# Pedalshield_Project_Schematic.net
KiCad netlist of a schematic drawn in Altium Designer
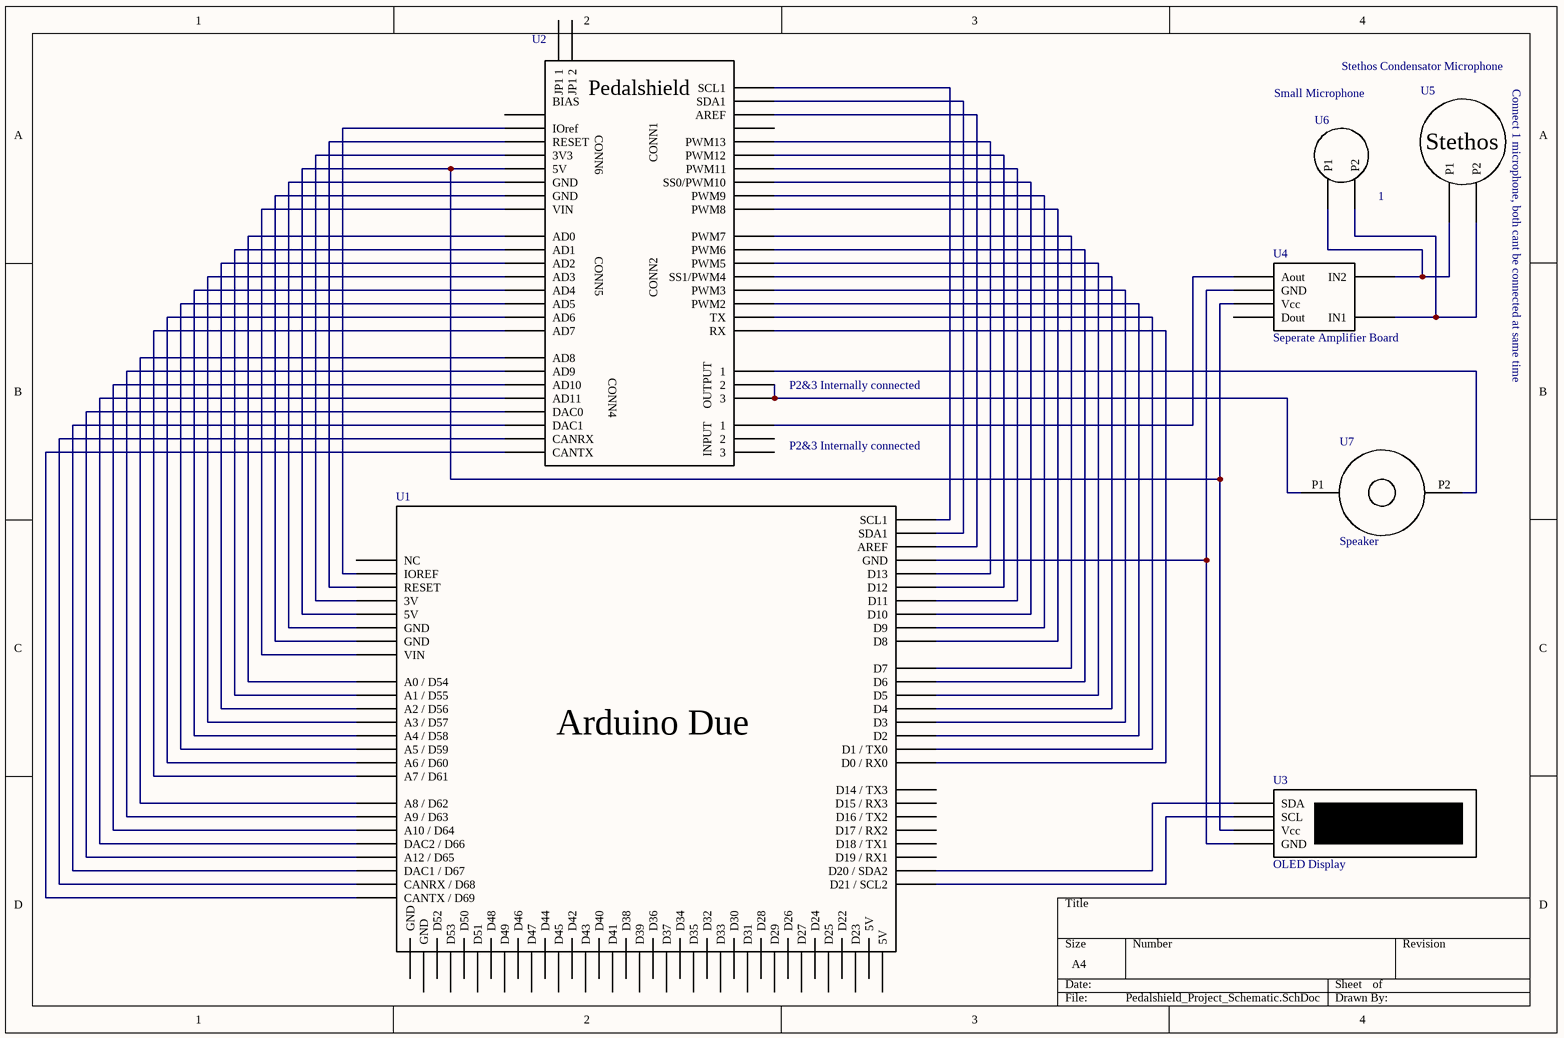
[diagram p0: Pedalshield_Project_Schematic.SchDoc]

(export (version "E")
  (design (tool "Eeschema 10.0.6"))
  (components
    (comp (ref "U1") (value "Arduino Due") (libsource (lib "Schlib1") (part "Arduino Due")))
    (comp (ref "U2") (value "1") (libsource (lib "Schlib1") (part "Pedalshield")))
    (comp (ref "U3") (value "OLED Display") (libsource (lib "Schlib1") (part "OLED Display")))
    (comp (ref "U4")
      (value "Seperate Amplifier Board")
      (libsource (lib "Schlib1") (part "Seperate Amplifier Board"))
    )
    (comp (ref "U5")
      (value "Stethos Condensator Microphone")
      (libsource (lib "Schlib1") (part "Stethos Condensator Microphone"))
    )
    (comp (ref "U6") (value "Small Microphone") (libsource (lib "Schlib1") (part "Small Microphone")))
    (comp (ref "U7") (value "Speaker") (libsource (lib "Schlib1") (part "Speaker")))
  )
  (nets
    (net (code "1") (name "Net-(U1-3V)") (class "Default")
      (node (ref "U1") (pin "SDA5") (pinfunction "3V_SDA5") (pintype "passive"))
      (node (ref "U2") (pin "SDA103") (pinfunction "3V3_SDA103") (pintype "passive"))
    )
    (net (code "2") (name "Net-(U1-A0_{slash}_D54)") (class "Default")
      (node (ref "U1") (pin "SDA11") (pinfunction "A0_/_D54_SDA11") (pintype "passive"))
      (node (ref "U2") (pin "SDA108") (pinfunction "AD0_SDA108") (pintype "passive"))
    )
    (net (code "3") (name "Net-(U1-A1_{slash}_D55)") (class "Default")
      (node (ref "U1") (pin "SDA12") (pinfunction "A1_/_D55_SDA12") (pintype "passive"))
      (node (ref "U2") (pin "SDA109") (pinfunction "AD1_SDA109") (pintype "passive"))
    )
    (net (code "4") (name "Net-(U1-A2_{slash}_D56)") (class "Default")
      (node (ref "U1") (pin "SDA13") (pinfunction "A2_/_D56_SDA13") (pintype "passive"))
      (node (ref "U2") (pin "SDA110") (pinfunction "AD2_SDA110") (pintype "passive"))
    )
    (net (code "5") (name "Net-(U1-A3_{slash}_D57)") (class "Default")
      (node (ref "U1") (pin "SDA14") (pinfunction "A3_/_D57_SDA14") (pintype "passive"))
      (node (ref "U2") (pin "SDA111") (pinfunction "AD3_SDA111") (pintype "passive"))
    )
    (net (code "6") (name "Net-(U1-A4_{slash}_D58)") (class "Default")
      (node (ref "U1") (pin "SDA15") (pinfunction "A4_/_D58_SDA15") (pintype "passive"))
      (node (ref "U2") (pin "SDA112") (pinfunction "AD4_SDA112") (pintype "passive"))
    )
    (net (code "7") (name "Net-(U1-A5_{slash}_D59)") (class "Default")
      (node (ref "U1") (pin "SDA16") (pinfunction "A5_/_D59_SDA16") (pintype "passive"))
      (node (ref "U2") (pin "SDA113") (pinfunction "AD5_SDA113") (pintype "passive"))
    )
    (net (code "8") (name "Net-(U1-A6_{slash}_D60)") (class "Default")
      (node (ref "U1") (pin "SDA17") (pinfunction "A6_/_D60_SDA17") (pintype "passive"))
      (node (ref "U2") (pin "SDA114") (pinfunction "AD6_SDA114") (pintype "passive"))
    )
    (net (code "9") (name "Net-(U1-A7_{slash}_D61)") (class "Default")
      (node (ref "U1") (pin "SDA18") (pinfunction "A7_/_D61_SDA18") (pintype "passive"))
      (node (ref "U2") (pin "SDA115") (pinfunction "AD7_SDA115") (pintype "passive"))
    )
    (net (code "10") (name "Net-(U1-A8_{slash}_D62)") (class "Default")
      (node (ref "U1") (pin "SDA20") (pinfunction "A8_/_D62_SDA20") (pintype "passive"))
      (node (ref "U2") (pin "SDA97") (pinfunction "AD8_SDA97") (pintype "passive"))
    )
    (net (code "11") (name "Net-(U1-A9_{slash}_D63)") (class "Default")
      (node (ref "U1") (pin "SDA21") (pinfunction "A9_/_D63_SDA21") (pintype "passive"))
      (node (ref "U2") (pin "SDA96") (pinfunction "AD9_SDA96") (pintype "passive"))
    )
    (net (code "12") (name "Net-(U1-A10_{slash}_D64)") (class "Default")
      (node (ref "U1") (pin "SDA22") (pinfunction "A10_/_D64_SDA22") (pintype "passive"))
      (node (ref "U2") (pin "SDA95") (pinfunction "AD10_SDA95") (pintype "passive"))
    )
    (net (code "13") (name "Net-(U1-A12_{slash}_D65)") (class "Default")
      (node (ref "U1") (pin "SDA24") (pinfunction "A12_/_D65_SDA24") (pintype "passive"))
      (node (ref "U2") (pin "SDA93") (pinfunction "DAC0_SDA93") (pintype "passive"))
    )
    (net (code "14") (name "Net-(U1-CANRX_{slash}_D68)") (class "Default")
      (node (ref "U1") (pin "SDA26") (pinfunction "CANRX_/_D68_SDA26") (pintype "passive"))
      (node (ref "U2") (pin "SDA91") (pinfunction "CANRX_SDA91") (pintype "passive"))
    )
    (net (code "15") (name "Net-(U1-CANTX_{slash}_D69)") (class "Default")
      (node (ref "U1") (pin "SDA27") (pinfunction "CANTX_/_D69_SDA27") (pintype "passive"))
      (node (ref "U2") (pin "SDA90") (pinfunction "CANTX_SDA90") (pintype "passive"))
    )
    (net (code "16") (name "Net-(U1-D0_{slash}_RX0)") (class "Default")
      (node (ref "U1") (pin "29") (pinfunction "D0_/_RX0_29") (pintype "passive"))
      (node (ref "U2") (pin "SDA88") (pinfunction "RX_SDA88") (pintype "passive"))
    )
    (net (code "17") (name "Net-(U1-D1_{slash}_TX0)") (class "Default")
      (node (ref "U1") (pin "28") (pinfunction "D1_/_TX0_28") (pintype "passive"))
      (node (ref "U2") (pin "SDA87") (pinfunction "TX_SDA87") (pintype "passive"))
    )
    (net (code "18") (name "Net-(U1-D2)") (class "Default")
      (node (ref "U1") (pin "27") (pinfunction "D2_27") (pintype "passive"))
      (node (ref "U2") (pin "SDA118") (pinfunction "PWM2_SDA118") (pintype "passive"))
    )
    (net (code "19") (name "Net-(U1-D3)") (class "Default")
      (node (ref "U1") (pin "26") (pinfunction "D3_26") (pintype "passive"))
      (node (ref "U2") (pin "SDA86") (pinfunction "PWM3_SDA86") (pintype "passive"))
    )
    (net (code "20") (name "Net-(U1-D4)") (class "Default")
      (node (ref "U1") (pin "25") (pinfunction "D4_25") (pintype "passive"))
      (node (ref "U2") (pin "SDA85") (pinfunction "SS1/PWM4_SDA85") (pintype "passive"))
    )
    (net (code "21") (name "Net-(U1-D5)") (class "Default")
      (node (ref "U1") (pin "24") (pinfunction "D5_24") (pintype "passive"))
      (node (ref "U2") (pin "SDA84") (pinfunction "PWM5_SDA84") (pintype "passive"))
    )
    (net (code "22") (name "Net-(U1-D6)") (class "Default")
      (node (ref "U1") (pin "23") (pinfunction "D6_23") (pintype "passive"))
      (node (ref "U2") (pin "SDA83") (pinfunction "PWM6_SDA83") (pintype "passive"))
    )
    (net (code "23") (name "Net-(U1-D7)") (class "Default")
      (node (ref "U1") (pin "22") (pinfunction "D7_22") (pintype "passive"))
      (node (ref "U2") (pin "SDA82") (pinfunction "PWM7_SDA82") (pintype "passive"))
    )
    (net (code "24") (name "Net-(U1-D8)") (class "Default")
      (node (ref "U1") (pin "21") (pinfunction "D8_21") (pintype "passive"))
      (node (ref "U2") (pin "SDA117") (pinfunction "PWM8_SDA117") (pintype "passive"))
    )
    (net (code "25") (name "Net-(U1-D9)") (class "Default")
      (node (ref "U1") (pin "20") (pinfunction "D9_20") (pintype "passive"))
      (node (ref "U2") (pin "SDA116") (pinfunction "PWM9_SDA116") (pintype "passive"))
    )
    (net (code "26") (name "Net-(U1-D10)") (class "Default")
      (node (ref "U1") (pin "19") (pinfunction "D10_19") (pintype "passive"))
      (node (ref "U2") (pin "SDA81") (pinfunction "SS0/PWM10_SDA81") (pintype "passive"))
    )
    (net (code "27") (name "Net-(U1-D11)") (class "Default")
      (node (ref "U1") (pin "18") (pinfunction "D11_18") (pintype "passive"))
      (node (ref "U2") (pin "SDA80") (pinfunction "PWM11_SDA80") (pintype "passive"))
    )
    (net (code "28") (name "Net-(U1-D12)") (class "Default")
      (node (ref "U1") (pin "17") (pinfunction "D12_17") (pintype "passive"))
      (node (ref "U2") (pin "SDA79") (pinfunction "PWM12_SDA79") (pintype "passive"))
    )
    (net (code "29") (name "Net-(U1-D13)") (class "Default")
      (node (ref "U1") (pin "16") (pinfunction "D13_16") (pintype "passive"))
      (node (ref "U2") (pin "SDA78") (pinfunction "PWM13_SDA78") (pintype "passive"))
    )
    (net (code "30") (name "Net-(U1-D20_{slash}_SDA2)") (class "Default")
      (node (ref "U1") (pin "36") (pinfunction "D20_/_SDA2_36") (pintype "passive"))
      (node (ref "U3") (pin "SDA69") (pinfunction "SDA_SDA69") (pintype "passive"))
    )
    (net (code "31") (name "Net-(U1-D21_{slash}_SCL2)") (class "Default")
      (node (ref "U1") (pin "37") (pinfunction "D21_/_SCL2_37") (pintype "passive"))
      (node (ref "U3") (pin "SDA70") (pinfunction "SCL_SDA70") (pintype "passive"))
    )
    (net (code "32") (name "Net-(U1-DAC1_{slash}_D67)") (class "Default")
      (node (ref "U1") (pin "SDA25") (pinfunction "DAC1_/_D67_SDA25") (pintype "passive"))
      (node (ref "U2") (pin "SDA92") (pinfunction "DAC1_SDA92") (pintype "passive"))
    )
    (net (code "33") (name "Net-(U1-DAC2_{slash}_D66)") (class "Default")
      (node (ref "U1") (pin "SDA23") (pinfunction "DAC2_/_D66_SDA23") (pintype "passive"))
      (node (ref "U2") (pin "SDA94") (pinfunction "AD11_SDA94") (pintype "passive"))
    )
    (net (code "34") (name "Net-(U1-GND-PadSDA7)") (class "Default")
      (node (ref "U1") (pin "SDA7") (pinfunction "GND_SDA7") (pintype "passive"))
      (node (ref "U2") (pin "SDA105") (pinfunction "GND_SDA105") (pintype "passive"))
    )
    (net (code "35") (name "Net-(U1-GND-PadSDA8)") (class "Default")
      (node (ref "U1") (pin "SDA8") (pinfunction "GND_SDA8") (pintype "passive"))
      (node (ref "U2") (pin "SDA106") (pinfunction "GND_SDA106") (pintype "passive"))
    )
    (net (code "36") (name "Net-(U1-IOREF)") (class "Default")
      (node (ref "U1") (pin "SDA3") (pinfunction "IOREF_SDA3") (pintype "passive"))
      (node (ref "U2") (pin "SDA101") (pinfunction "IOref_SDA101") (pintype "passive"))
    )
    (net (code "37") (name "Net-(U1-RESET)") (class "Default")
      (node (ref "U1") (pin "SDA4") (pinfunction "RESET_SDA4") (pintype "passive"))
      (node (ref "U2") (pin "SDA102") (pinfunction "RESET_SDA102") (pintype "passive"))
    )
    (net (code "38") (name "Net-(U1-VIN)") (class "Default")
      (node (ref "U1") (pin "SDA9") (pinfunction "VIN_SDA9") (pintype "passive"))
      (node (ref "U2") (pin "SDA107") (pinfunction "VIN_SDA107") (pintype "passive"))
    )
    (net (code "39") (name "Net-(U2-1-PadSDA119)") (class "Default")
      (node (ref "U2") (pin "SDA119") (pinfunction "1_SDA119") (pintype "passive"))
      (node (ref "U7") (pin "P2") (pinfunction "P2_P2") (pintype "passive"))
    )
    (net (code "40") (name "Net-(U2-2-PadSDA120)") (class "Default")
      (node (ref "U2") (pin "SDA120") (pinfunction "2_SDA120") (pintype "passive"))
      (node (ref "U2") (pin "SDA121") (pinfunction "3_SDA121") (pintype "passive"))
      (node (ref "U7") (pin "P1") (pinfunction "P1_P1") (pintype "passive"))
    )
    (net (code "41") (name "Net-(U2-5V)") (class "Default")
      (node (ref "U1") (pin "SDA6") (pinfunction "5V_SDA6") (pintype "passive"))
      (node (ref "U2") (pin "SDA104") (pinfunction "5V_SDA104") (pintype "passive"))
      (node (ref "U3") (pin "SDA71") (pinfunction "Vcc_SDA71") (pintype "passive"))
      (node (ref "U4") (pin "SDA64") (pinfunction "Vcc_SDA64") (pintype "passive"))
    )
    (net (code "42") (name "Net-(U2-AREF)") (class "Default")
      (node (ref "U1") (pin "AREF") (pinfunction "AREF_AREF") (pintype "passive"))
      (node (ref "U2") (pin "SDA76") (pinfunction "AREF_SDA76") (pintype "passive"))
    )
    (net (code "43") (name "Net-(U2-SCL1)") (class "Default")
      (node (ref "U1") (pin "SCL1") (pinfunction "SCL1_SCL1") (pintype "passive"))
      (node (ref "U2") (pin "SDA74") (pinfunction "SCL1_SDA74") (pintype "passive"))
    )
    (net (code "44") (name "Net-(U2-SDA1)") (class "Default")
      (node (ref "U1") (pin "SDA1") (pinfunction "SDA1_SDA1") (pintype "passive"))
      (node (ref "U2") (pin "SDA75") (pinfunction "SDA1_SDA75") (pintype "passive"))
    )
    (net (code "45") (name "Net-(U3-GND)") (class "Default")
      (node (ref "U1") (pin "GND") (pinfunction "GND_GND") (pintype "passive"))
      (node (ref "U3") (pin "SDA72") (pinfunction "GND_SDA72") (pintype "passive"))
      (node (ref "U4") (pin "SDA65") (pinfunction "GND_SDA65") (pintype "passive"))
    )
    (net (code "46") (name "Net-(U4-Aout)") (class "Default")
      (node (ref "U2") (pin "SDA122") (pinfunction "1_SDA122") (pintype "passive"))
      (node (ref "U4") (pin "SDA66") (pinfunction "Aout_SDA66") (pintype "passive"))
    )
    (net (code "47") (name "Net-(U4-IN1)") (class "Default")
      (node (ref "U4") (pin "SDA67") (pinfunction "IN1_SDA67") (pintype "passive"))
      (node (ref "U5") (pin "SDA67") (pinfunction "P2_SDA67") (pintype "passive"))
      (node (ref "U6") (pin "SDA67") (pinfunction "P2_SDA67") (pintype "passive"))
    )
    (net (code "48") (name "Net-(U4-IN2)") (class "Default")
      (node (ref "U4") (pin "SDA68") (pinfunction "IN2_SDA68") (pintype "passive"))
      (node (ref "U5") (pin "SDA68") (pinfunction "P1_SDA68") (pintype "passive"))
      (node (ref "U6") (pin "SDA68") (pinfunction "P1_SDA68") (pintype "passive"))
    )
    (net (code "49") (name "unconnected-(U1-5V-PadSDA28)") (class "Default")
      (node (ref "U1") (pin "SDA28") (pinfunction "5V_SDA28") (pintype "passive"))
    )
    (net (code "50") (name "unconnected-(U1-5V-PadSDA29)") (class "Default")
      (node (ref "U1") (pin "SDA29") (pinfunction "5V_SDA29") (pintype "passive"))
    )
    (net (code "51") (name "unconnected-(U1-D14_{slash}_TX3-Pad30)") (class "Default")
      (node (ref "U1") (pin "30") (pinfunction "D14_/_TX3_30") (pintype "passive"))
    )
    (net (code "52") (name "unconnected-(U1-D15_{slash}_RX3-Pad31)") (class "Default")
      (node (ref "U1") (pin "31") (pinfunction "D15_/_RX3_31") (pintype "passive"))
    )
    (net (code "53") (name "unconnected-(U1-D16_{slash}_TX2-Pad32)") (class "Default")
      (node (ref "U1") (pin "32") (pinfunction "D16_/_TX2_32") (pintype "passive"))
    )
    (net (code "54") (name "unconnected-(U1-D17_{slash}_RX2-Pad33)") (class "Default")
      (node (ref "U1") (pin "33") (pinfunction "D17_/_RX2_33") (pintype "passive"))
    )
    (net (code "55") (name "unconnected-(U1-D18_{slash}_TX1-Pad34)") (class "Default")
      (node (ref "U1") (pin "34") (pinfunction "D18_/_TX1_34") (pintype "passive"))
    )
    (net (code "56") (name "unconnected-(U1-D19_{slash}_RX1-Pad35)") (class "Default")
      (node (ref "U1") (pin "35") (pinfunction "D19_/_RX1_35") (pintype "passive"))
    )
    (net (code "57") (name "unconnected-(U1-D22-PadSDA31)") (class "Default")
      (node (ref "U1") (pin "SDA31") (pinfunction "D22_SDA31") (pintype "passive"))
    )
    (net (code "58") (name "unconnected-(U1-D23-PadSDA30)") (class "Default")
      (node (ref "U1") (pin "SDA30") (pinfunction "D23_SDA30") (pintype "passive"))
    )
    (net (code "59") (name "unconnected-(U1-D24-PadSDA33)") (class "Default")
      (node (ref "U1") (pin "SDA33") (pinfunction "D24_SDA33") (pintype "passive"))
    )
    (net (code "60") (name "unconnected-(U1-D25-PadSDA32)") (class "Default")
      (node (ref "U1") (pin "SDA32") (pinfunction "D25_SDA32") (pintype "passive"))
    )
    (net (code "61") (name "unconnected-(U1-D26-PadSDA35)") (class "Default")
      (node (ref "U1") (pin "SDA35") (pinfunction "D26_SDA35") (pintype "passive"))
    )
    (net (code "62") (name "unconnected-(U1-D27-PadSDA34)") (class "Default")
      (node (ref "U1") (pin "SDA34") (pinfunction "D27_SDA34") (pintype "passive"))
    )
    (net (code "63") (name "unconnected-(U1-D28-PadSDA37)") (class "Default")
      (node (ref "U1") (pin "SDA37") (pinfunction "D28_SDA37") (pintype "passive"))
    )
    (net (code "64") (name "unconnected-(U1-D29-PadSDA36)") (class "Default")
      (node (ref "U1") (pin "SDA36") (pinfunction "D29_SDA36") (pintype "passive"))
    )
    (net (code "65") (name "unconnected-(U1-D30-PadSDA39)") (class "Default")
      (node (ref "U1") (pin "SDA39") (pinfunction "D30_SDA39") (pintype "passive"))
    )
    (net (code "66") (name "unconnected-(U1-D31-PadSDA38)") (class "Default")
      (node (ref "U1") (pin "SDA38") (pinfunction "D31_SDA38") (pintype "passive"))
    )
    (net (code "67") (name "unconnected-(U1-D32-PadSDA41)") (class "Default")
      (node (ref "U1") (pin "SDA41") (pinfunction "D32_SDA41") (pintype "passive"))
    )
    (net (code "68") (name "unconnected-(U1-D33-PadSDA40)") (class "Default")
      (node (ref "U1") (pin "SDA40") (pinfunction "D33_SDA40") (pintype "passive"))
    )
    (net (code "69") (name "unconnected-(U1-D34-PadSDA43)") (class "Default")
      (node (ref "U1") (pin "SDA43") (pinfunction "D34_SDA43") (pintype "passive"))
    )
    (net (code "70") (name "unconnected-(U1-D35-PadSDA42)") (class "Default")
      (node (ref "U1") (pin "SDA42") (pinfunction "D35_SDA42") (pintype "passive"))
    )
    (net (code "71") (name "unconnected-(U1-D36-PadSDA45)") (class "Default")
      (node (ref "U1") (pin "SDA45") (pinfunction "D36_SDA45") (pintype "passive"))
    )
    (net (code "72") (name "unconnected-(U1-D37-PadSDA44)") (class "Default")
      (node (ref "U1") (pin "SDA44") (pinfunction "D37_SDA44") (pintype "passive"))
    )
    (net (code "73") (name "unconnected-(U1-D38-PadSDA47)") (class "Default")
      (node (ref "U1") (pin "SDA47") (pinfunction "D38_SDA47") (pintype "passive"))
    )
    (net (code "74") (name "unconnected-(U1-D39-PadSDA46)") (class "Default")
      (node (ref "U1") (pin "SDA46") (pinfunction "D39_SDA46") (pintype "passive"))
    )
    (net (code "75") (name "unconnected-(U1-D40-PadSDA56)") (class "Default")
      (node (ref "U1") (pin "SDA56") (pinfunction "D40_SDA56") (pintype "passive"))
    )
    (net (code "76") (name "unconnected-(U1-D41-PadSDA48)") (class "Default")
      (node (ref "U1") (pin "SDA48") (pinfunction "D41_SDA48") (pintype "passive"))
    )
    (net (code "77") (name "unconnected-(U1-D42-PadSDA57)") (class "Default")
      (node (ref "U1") (pin "SDA57") (pinfunction "D42_SDA57") (pintype "passive"))
    )
    (net (code "78") (name "unconnected-(U1-D43-PadSDA49)") (class "Default")
      (node (ref "U1") (pin "SDA49") (pinfunction "D43_SDA49") (pintype "passive"))
    )
    (net (code "79") (name "unconnected-(U1-D44-PadSDA58)") (class "Default")
      (node (ref "U1") (pin "SDA58") (pinfunction "D44_SDA58") (pintype "passive"))
    )
    (net (code "80") (name "unconnected-(U1-D45-PadSDA50)") (class "Default")
      (node (ref "U1") (pin "SDA50") (pinfunction "D45_SDA50") (pintype "passive"))
    )
    (net (code "81") (name "unconnected-(U1-D46-PadSDA59)") (class "Default")
      (node (ref "U1") (pin "SDA59") (pinfunction "D46_SDA59") (pintype "passive"))
    )
    (net (code "82") (name "unconnected-(U1-D47-PadSDA51)") (class "Default")
      (node (ref "U1") (pin "SDA51") (pinfunction "D47_SDA51") (pintype "passive"))
    )
    (net (code "83") (name "unconnected-(U1-D48-PadSDA60)") (class "Default")
      (node (ref "U1") (pin "SDA60") (pinfunction "D48_SDA60") (pintype "passive"))
    )
    (net (code "84") (name "unconnected-(U1-D49-PadSDA52)") (class "Default")
      (node (ref "U1") (pin "SDA52") (pinfunction "D49_SDA52") (pintype "passive"))
    )
    (net (code "85") (name "unconnected-(U1-D50-PadSDA61)") (class "Default")
      (node (ref "U1") (pin "SDA61") (pinfunction "D50_SDA61") (pintype "passive"))
    )
    (net (code "86") (name "unconnected-(U1-D51-PadSDA53)") (class "Default")
      (node (ref "U1") (pin "SDA53") (pinfunction "D51_SDA53") (pintype "passive"))
    )
    (net (code "87") (name "unconnected-(U1-D52-PadSDA62)") (class "Default")
      (node (ref "U1") (pin "SDA62") (pinfunction "D52_SDA62") (pintype "passive"))
    )
    (net (code "88") (name "unconnected-(U1-D53-PadSDA54)") (class "Default")
      (node (ref "U1") (pin "SDA54") (pinfunction "D53_SDA54") (pintype "passive"))
    )
    (net (code "89") (name "unconnected-(U1-GND-PadSDA55)") (class "Default")
      (node (ref "U1") (pin "SDA55") (pinfunction "GND_SDA55") (pintype "passive"))
    )
    (net (code "90") (name "unconnected-(U1-GND-PadSDA55)_1") (class "Default")
      (node (ref "U1") (pin "SDA55") (pinfunction "GND_SDA55") (pintype "passive"))
    )
    (net (code "91") (name "unconnected-(U1-NC-PadSDA2)") (class "Default")
      (node (ref "U1") (pin "SDA2") (pinfunction "NC_SDA2") (pintype "passive"))
    )
    (net (code "92") (name "unconnected-(U2-2-PadSDA123)") (class "Default")
      (node (ref "U2") (pin "SDA123") (pinfunction "2_SDA123") (pintype "passive"))
    )
    (net (code "93") (name "unconnected-(U2-3-PadSDA124)") (class "Default")
      (node (ref "U2") (pin "SDA124") (pinfunction "3_SDA124") (pintype "passive"))
    )
    (net (code "94") (name "unconnected-(U2-JP1_1-PadSDA98)") (class "Default")
      (node (ref "U2") (pin "SDA98") (pinfunction "JP1_1_SDA98") (pintype "passive"))
    )
    (net (code "95") (name "unconnected-(U2-JP1_2-PadSDA99)") (class "Default")
      (node (ref "U2") (pin "SDA99") (pinfunction "JP1_2_SDA99") (pintype "passive"))
    )
    (net (code "96") (name "unconnected-(U2-PadSDA77)") (class "Default")
      (node (ref "U2") (pin "SDA77") (pinfunction "SDA77_SDA77") (pintype "passive"))
    )
    (net (code "97") (name "unconnected-(U2-PadSDA100)") (class "Default")
      (node (ref "U2") (pin "SDA100") (pinfunction "SDA100_SDA100") (pintype "passive"))
    )
    (net (code "98") (name "unconnected-(U4-Dout-PadSDA63)") (class "Default")
      (node (ref "U4") (pin "SDA63") (pinfunction "Dout_SDA63") (pintype "passive"))
    )
  )
)
